# icmu150_n32_dp.net
KiCad netlist of a schematic drawn in Altium Designer
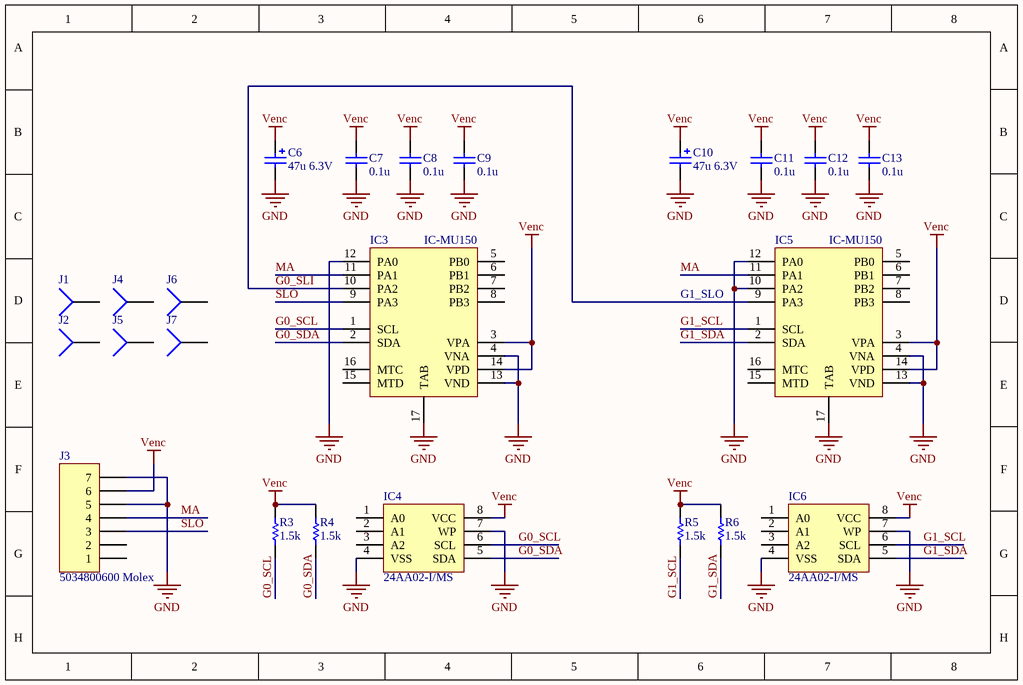
[diagram p0: icmu150_n32_dp.SchDoc]

(export (version "E")
  (design (tool "Eeschema 10.0.6"))
  (components
    (comp (ref "C6")
      (value "47u 6.3V")
      (footprint "RC_0805_T0.8")
      (description "Polarized Capacitor (Axial)")
      (fields (field (name "MANUFACTURER") "Yageo"))
      (libsource (lib "Miscellaneous Devices") (part "Cap Pol2"))
    )
    (comp (ref "C7")
      (value "0.1u")
      (footprint "RC_0402_T0.55")
      (description "Capacitor")
      (fields (field (name "MANUFACTURER") "Yageo"))
      (libsource (lib "Miscellaneous Devices") (part "Cap"))
    )
    (comp (ref "C8")
      (value "0.1u")
      (footprint "RC_0402_T0.55")
      (description "Capacitor")
      (fields (field (name "MANUFACTURER") "Yageo"))
      (libsource (lib "Miscellaneous Devices") (part "Cap"))
    )
    (comp (ref "C9")
      (value "0.1u")
      (footprint "RC_0402_T0.55")
      (description "Capacitor")
      (fields (field (name "MANUFACTURER") "Yageo"))
      (libsource (lib "Miscellaneous Devices") (part "Cap"))
    )
    (comp (ref "C10")
      (value "47u 6.3V")
      (footprint "RC_0805_T0.8")
      (description "Polarized Capacitor (Axial)")
      (fields (field (name "MANUFACTURER") "Yageo"))
      (libsource (lib "Miscellaneous Devices") (part "Cap Pol2"))
    )
    (comp (ref "C11")
      (value "0.1u")
      (footprint "RC_0402_T0.55")
      (description "Capacitor")
      (fields (field (name "MANUFACTURER") "Yageo"))
      (libsource (lib "Miscellaneous Devices") (part "Cap"))
    )
    (comp (ref "C12")
      (value "0.1u")
      (footprint "RC_0402_T0.55")
      (description "Capacitor")
      (fields (field (name "MANUFACTURER") "Yageo"))
      (libsource (lib "Miscellaneous Devices") (part "Cap"))
    )
    (comp (ref "C13")
      (value "0.1u")
      (footprint "RC_0402_T0.55")
      (description "Capacitor")
      (fields (field (name "MANUFACTURER") "Yageo"))
      (libsource (lib "Miscellaneous Devices") (part "Cap"))
    )
    (comp (ref "IC3")
      (value "IC-MU150")
      (footprint "RR_DFN16")
      (description "Magnetic Encoder")
      (fields (field (name "MANUFACTURER") "iC-Haus"))
      (libsource (lib "Schlib1") (part "IC-MU150"))
    )
    (comp (ref "IC4")
      (value "24AA02-I/MS")
      (footprint "RR_MSOP8")
      (fields (field (name "MANUFACTURER") "Microchip Technology"))
      (libsource (lib "Schlib1") (part "24AA02-I/SM"))
    )
    (comp (ref "IC5")
      (value "IC-MU150")
      (footprint "RR_DFN16")
      (description "Magnetic Encoder")
      (fields (field (name "MANUFACTURER") "iC-Haus"))
      (libsource (lib "Schlib1") (part "IC-MU150"))
    )
    (comp (ref "IC6")
      (value "24AA02-I/MS")
      (footprint "RR_MSOP8")
      (fields (field (name "MANUFACTURER") "Microchip Technology"))
      (libsource (lib "Schlib1") (part "24AA02-I/SM"))
    )
    (comp (ref "J1")
      (value "Socket")
      (footprint "PIN")
      (libsource (lib "Miscellaneous Connectors") (part "Socket"))
    )
    (comp (ref "J2")
      (value "Socket")
      (footprint "PIN")
      (libsource (lib "Miscellaneous Connectors") (part "Socket"))
    )
    (comp (ref "J3")
      (value "5034800600 Molex")
      (footprint "RR_CONN_FPC_6_05_MOLEX wo pad")
      (description "Header, 7-Pin")
      (fields (field (name "MANUFACTURER") "Molex"))
      (libsource (lib "Miscellaneous Connectors") (part "Header 7"))
    )
    (comp (ref "J4")
      (value "Socket")
      (footprint "PIN")
      (libsource (lib "Miscellaneous Connectors") (part "Socket"))
    )
    (comp (ref "J5")
      (value "Socket")
      (footprint "PIN")
      (libsource (lib "Miscellaneous Connectors") (part "Socket"))
    )
    (comp (ref "J6")
      (value "Socket")
      (footprint "PIN")
      (libsource (lib "Miscellaneous Connectors") (part "Socket"))
    )
    (comp (ref "J7")
      (value "Socket")
      (footprint "PIN")
      (libsource (lib "Miscellaneous Connectors") (part "Socket"))
    )
    (comp (ref "R3")
      (value "1.5k")
      (footprint "RR_0402")
      (description "Resistor")
      (fields (field (name "MANUFACTURER") "Yageo"))
      (libsource (lib "Miscellaneous Devices") (part "Res1"))
    )
    (comp (ref "R4")
      (value "1.5k")
      (footprint "RR_0402")
      (description "Resistor")
      (fields (field (name "MANUFACTURER") "Yageo"))
      (libsource (lib "Miscellaneous Devices") (part "Res1"))
    )
    (comp (ref "R5")
      (value "1.5k")
      (footprint "RR_0402")
      (description "Resistor")
      (fields (field (name "MANUFACTURER") "Yageo"))
      (libsource (lib "Miscellaneous Devices") (part "Res1"))
    )
    (comp (ref "R6")
      (value "1.5k")
      (footprint "RR_0402")
      (description "Resistor")
      (fields (field (name "MANUFACTURER") "Yageo"))
      (libsource (lib "Miscellaneous Devices") (part "Res1"))
    )
  )
  (nets
    (net (code "1") (name "/G0_SCL") (class "Default")
      (node (ref "IC3") (pin "1") (pinfunction "SCL_1") (pintype "passive"))
      (node (ref "IC4") (pin "6") (pinfunction "SCL_6") (pintype "passive"))
      (node (ref "R3") (pin "2") (pinfunction "2_2") (pintype "passive"))
    )
    (net (code "2") (name "/G0_SDA") (class "Default")
      (node (ref "IC3") (pin "2") (pinfunction "SDA_2") (pintype "passive"))
      (node (ref "IC4") (pin "5") (pinfunction "SDA_5") (pintype "passive"))
      (node (ref "R4") (pin "2") (pinfunction "2_2") (pintype "passive"))
    )
    (net (code "3") (name "/G0_SLI") (class "Default")
      (node (ref "IC3") (pin "10") (pinfunction "PA2_10") (pintype "passive"))
      (node (ref "IC5") (pin "9") (pinfunction "PA3_9") (pintype "passive"))
    )
    (net (code "4") (name "/G1_SCL") (class "Default")
      (node (ref "IC5") (pin "1") (pinfunction "SCL_1") (pintype "passive"))
      (node (ref "IC6") (pin "6") (pinfunction "SCL_6") (pintype "passive"))
      (node (ref "R5") (pin "2") (pinfunction "2_2") (pintype "passive"))
    )
    (net (code "5") (name "/G1_SDA") (class "Default")
      (node (ref "IC5") (pin "2") (pinfunction "SDA_2") (pintype "passive"))
      (node (ref "IC6") (pin "5") (pinfunction "SDA_5") (pintype "passive"))
      (node (ref "R6") (pin "2") (pinfunction "2_2") (pintype "passive"))
    )
    (net (code "6") (name "/MA") (class "Default")
      (node (ref "IC3") (pin "11") (pinfunction "PA1_11") (pintype "passive"))
      (node (ref "IC5") (pin "11") (pinfunction "PA1_11") (pintype "passive"))
      (node (ref "J3") (pin "4") (pinfunction "4_4") (pintype "passive"))
    )
    (net (code "7") (name "/SLO") (class "Default")
      (node (ref "IC3") (pin "9") (pinfunction "PA3_9") (pintype "passive"))
      (node (ref "J3") (pin "3") (pinfunction "3_3") (pintype "passive"))
    )
    (net (code "8") (name "GND") (class "Default")
      (node (ref "C10") (pin "2") (pinfunction "2_2") (pintype "passive"))
      (node (ref "C11") (pin "2") (pinfunction "2_2") (pintype "passive"))
      (node (ref "C12") (pin "2") (pinfunction "2_2") (pintype "passive"))
      (node (ref "C13") (pin "2") (pinfunction "2_2") (pintype "passive"))
      (node (ref "C6") (pin "2") (pinfunction "2_2") (pintype "passive"))
      (node (ref "C7") (pin "2") (pinfunction "2_2") (pintype "passive"))
      (node (ref "C8") (pin "2") (pinfunction "2_2") (pintype "passive"))
      (node (ref "C9") (pin "2") (pinfunction "2_2") (pintype "passive"))
      (node (ref "IC3") (pin "12") (pinfunction "PA0_12") (pintype "passive"))
      (node (ref "IC3") (pin "13") (pinfunction "VND_13") (pintype "passive"))
      (node (ref "IC3") (pin "17") (pinfunction "TAB_17") (pintype "passive"))
      (node (ref "IC3") (pin "4") (pinfunction "VNA_4") (pintype "passive"))
      (node (ref "IC4") (pin "4") (pinfunction "VSS_4") (pintype "passive"))
      (node (ref "IC4") (pin "7") (pinfunction "WP_7") (pintype "passive"))
      (node (ref "IC5") (pin "10") (pinfunction "PA2_10") (pintype "passive"))
      (node (ref "IC5") (pin "12") (pinfunction "PA0_12") (pintype "passive"))
      (node (ref "IC5") (pin "13") (pinfunction "VND_13") (pintype "passive"))
      (node (ref "IC5") (pin "17") (pinfunction "TAB_17") (pintype "passive"))
      (node (ref "IC5") (pin "4") (pinfunction "VNA_4") (pintype "passive"))
      (node (ref "IC6") (pin "4") (pinfunction "VSS_4") (pintype "passive"))
      (node (ref "IC6") (pin "7") (pinfunction "WP_7") (pintype "passive"))
      (node (ref "J3") (pin "5") (pinfunction "5_5") (pintype "passive"))
      (node (ref "J3") (pin "7") (pinfunction "7_7") (pintype "passive"))
    )
    (net (code "9") (name "Venc") (class "Default")
      (node (ref "C10") (pin "1") (pinfunction "1_1") (pintype "passive"))
      (node (ref "C11") (pin "1") (pinfunction "1_1") (pintype "passive"))
      (node (ref "C12") (pin "1") (pinfunction "1_1") (pintype "passive"))
      (node (ref "C13") (pin "1") (pinfunction "1_1") (pintype "passive"))
      (node (ref "C6") (pin "1") (pinfunction "1_1") (pintype "passive"))
      (node (ref "C7") (pin "1") (pinfunction "1_1") (pintype "passive"))
      (node (ref "C8") (pin "1") (pinfunction "1_1") (pintype "passive"))
      (node (ref "C9") (pin "1") (pinfunction "1_1") (pintype "passive"))
      (node (ref "IC3") (pin "14") (pinfunction "VPD_14") (pintype "passive"))
      (node (ref "IC3") (pin "3") (pinfunction "VPA_3") (pintype "passive"))
      (node (ref "IC4") (pin "8") (pinfunction "VCC_8") (pintype "passive"))
      (node (ref "IC5") (pin "14") (pinfunction "VPD_14") (pintype "passive"))
      (node (ref "IC5") (pin "3") (pinfunction "VPA_3") (pintype "passive"))
      (node (ref "IC6") (pin "8") (pinfunction "VCC_8") (pintype "passive"))
      (node (ref "J3") (pin "6") (pinfunction "6_6") (pintype "passive"))
      (node (ref "R3") (pin "1") (pinfunction "1_1") (pintype "passive"))
      (node (ref "R4") (pin "1") (pinfunction "1_1") (pintype "passive"))
      (node (ref "R5") (pin "1") (pinfunction "1_1") (pintype "passive"))
      (node (ref "R6") (pin "1") (pinfunction "1_1") (pintype "passive"))
    )
    (net (code "10") (name "unconnected-(IC3-MTC-Pad16)") (class "Default")
      (node (ref "IC3") (pin "16") (pinfunction "MTC_16") (pintype "passive"))
    )
    (net (code "11") (name "unconnected-(IC3-MTD-Pad15)") (class "Default")
      (node (ref "IC3") (pin "15") (pinfunction "MTD_15") (pintype "passive"))
    )
    (net (code "12") (name "unconnected-(IC3-PB0-Pad5)") (class "Default")
      (node (ref "IC3") (pin "5") (pinfunction "PB0_5") (pintype "passive"))
    )
    (net (code "13") (name "unconnected-(IC3-PB1-Pad6)") (class "Default")
      (node (ref "IC3") (pin "6") (pinfunction "PB1_6") (pintype "passive"))
    )
    (net (code "14") (name "unconnected-(IC3-PB2-Pad7)") (class "Default")
      (node (ref "IC3") (pin "7") (pinfunction "PB2_7") (pintype "passive"))
    )
    (net (code "15") (name "unconnected-(IC3-PB3-Pad8)") (class "Default")
      (node (ref "IC3") (pin "8") (pinfunction "PB3_8") (pintype "passive"))
    )
    (net (code "16") (name "unconnected-(IC4-A0-Pad1)") (class "Default")
      (node (ref "IC4") (pin "1") (pinfunction "A0_1") (pintype "passive"))
    )
    (net (code "17") (name "unconnected-(IC4-A1-Pad2)") (class "Default")
      (node (ref "IC4") (pin "2") (pinfunction "A1_2") (pintype "passive"))
    )
    (net (code "18") (name "unconnected-(IC4-A2-Pad3)") (class "Default")
      (node (ref "IC4") (pin "3") (pinfunction "A2_3") (pintype "passive"))
    )
    (net (code "19") (name "unconnected-(IC5-MTC-Pad16)") (class "Default")
      (node (ref "IC5") (pin "16") (pinfunction "MTC_16") (pintype "passive"))
    )
    (net (code "20") (name "unconnected-(IC5-MTD-Pad15)") (class "Default")
      (node (ref "IC5") (pin "15") (pinfunction "MTD_15") (pintype "passive"))
    )
    (net (code "21") (name "unconnected-(IC5-PB0-Pad5)") (class "Default")
      (node (ref "IC5") (pin "5") (pinfunction "PB0_5") (pintype "passive"))
    )
    (net (code "22") (name "unconnected-(IC5-PB1-Pad6)") (class "Default")
      (node (ref "IC5") (pin "6") (pinfunction "PB1_6") (pintype "passive"))
    )
    (net (code "23") (name "unconnected-(IC5-PB2-Pad7)") (class "Default")
      (node (ref "IC5") (pin "7") (pinfunction "PB2_7") (pintype "passive"))
    )
    (net (code "24") (name "unconnected-(IC5-PB3-Pad8)") (class "Default")
      (node (ref "IC5") (pin "8") (pinfunction "PB3_8") (pintype "passive"))
    )
    (net (code "25") (name "unconnected-(IC6-A0-Pad1)") (class "Default")
      (node (ref "IC6") (pin "1") (pinfunction "A0_1") (pintype "passive"))
    )
    (net (code "26") (name "unconnected-(IC6-A1-Pad2)") (class "Default")
      (node (ref "IC6") (pin "2") (pinfunction "A1_2") (pintype "passive"))
    )
    (net (code "27") (name "unconnected-(IC6-A2-Pad3)") (class "Default")
      (node (ref "IC6") (pin "3") (pinfunction "A2_3") (pintype "passive"))
    )
    (net (code "28") (name "unconnected-(J1-Pad1)") (class "Default")
      (node (ref "J1") (pin "1") (pinfunction "1_1") (pintype "passive"))
    )
    (net (code "29") (name "unconnected-(J2-Pad1)") (class "Default")
      (node (ref "J2") (pin "1") (pinfunction "1_1") (pintype "passive"))
    )
    (net (code "30") (name "unconnected-(J3-Pad1)") (class "Default")
      (node (ref "J3") (pin "1") (pinfunction "1_1") (pintype "passive"))
    )
    (net (code "31") (name "unconnected-(J3-Pad2)") (class "Default")
      (node (ref "J3") (pin "2") (pinfunction "2_2") (pintype "passive"))
    )
    (net (code "32") (name "unconnected-(J4-Pad1)") (class "Default")
      (node (ref "J4") (pin "1") (pinfunction "1_1") (pintype "passive"))
    )
    (net (code "33") (name "unconnected-(J5-Pad1)") (class "Default")
      (node (ref "J5") (pin "1") (pinfunction "1_1") (pintype "passive"))
    )
    (net (code "34") (name "unconnected-(J6-Pad1)") (class "Default")
      (node (ref "J6") (pin "1") (pinfunction "1_1") (pintype "passive"))
    )
    (net (code "35") (name "unconnected-(J7-Pad1)") (class "Default")
      (node (ref "J7") (pin "1") (pinfunction "1_1") (pintype "passive"))
    )
  )
)
